# auxDaqUnitTop2022.net
KiCad netlist of a schematic drawn in EAGLE
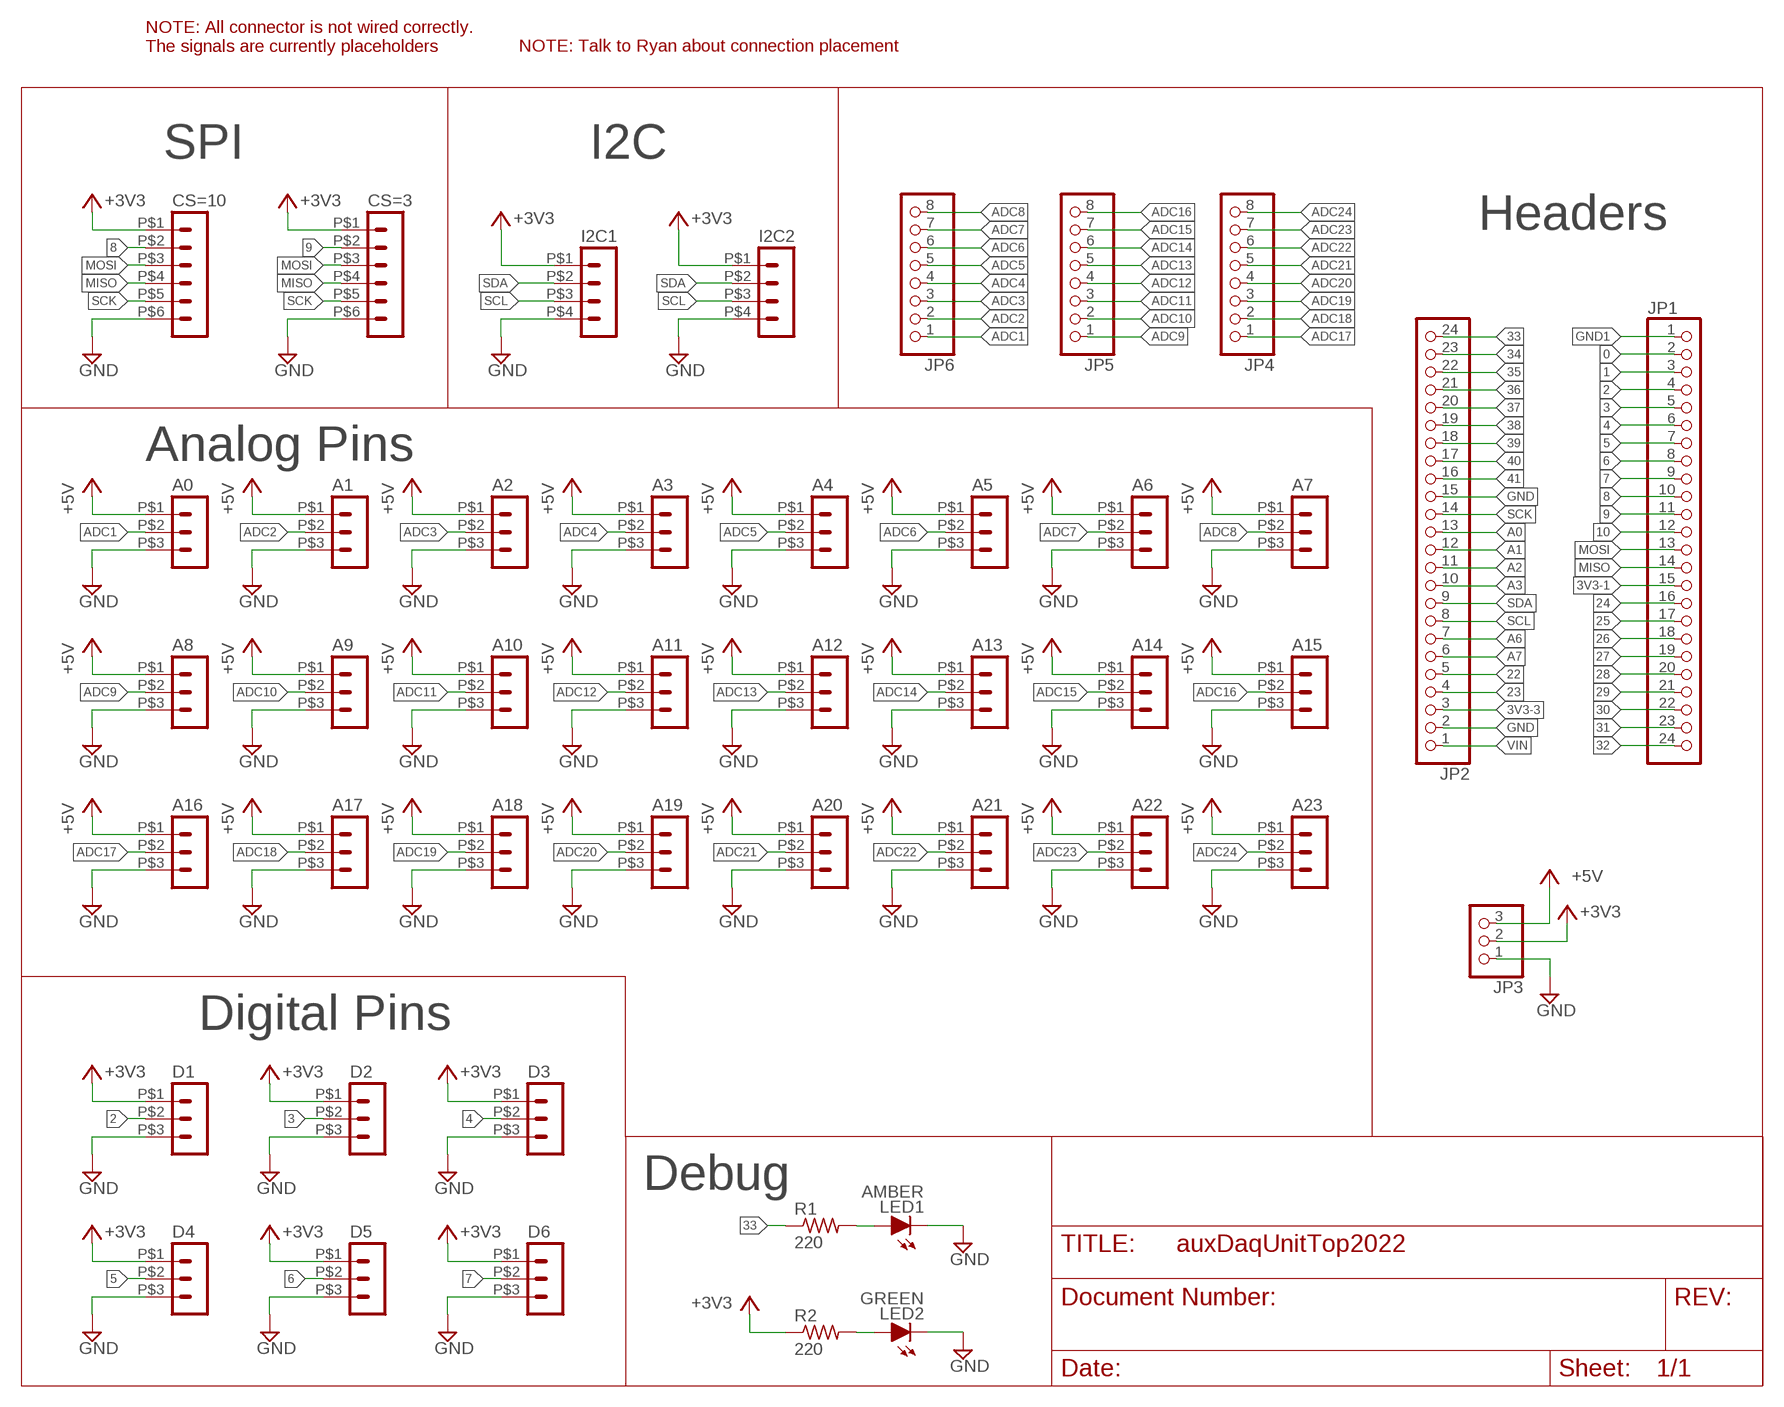
[diagram p0: schematic, sheet 1]

(export (version "E")
  (design (tool "Eeschema 10.0.6"))
  (components
    (comp (ref "A0")
      (value "HEADER_POS3_43650-0300")
      (footprint "eagle-import:43650-0300")
      (libsource (lib "eagle-import") (part "HEADER_POS3_?43650-0300"))
    )
    (comp (ref "A1")
      (value "HEADER_POS3_43650-0300")
      (footprint "eagle-import:43650-0300")
      (libsource (lib "eagle-import") (part "HEADER_POS3_?43650-0300"))
    )
    (comp (ref "A2")
      (value "HEADER_POS3_43650-0300")
      (footprint "eagle-import:43650-0300")
      (libsource (lib "eagle-import") (part "HEADER_POS3_?43650-0300"))
    )
    (comp (ref "A3")
      (value "HEADER_POS3_43650-0300")
      (footprint "eagle-import:43650-0300")
      (libsource (lib "eagle-import") (part "HEADER_POS3_?43650-0300"))
    )
    (comp (ref "A4")
      (value "HEADER_POS3_43650-0300")
      (footprint "eagle-import:43650-0300")
      (libsource (lib "eagle-import") (part "HEADER_POS3_?43650-0300"))
    )
    (comp (ref "A5")
      (value "HEADER_POS3_43650-0300")
      (footprint "eagle-import:43650-0300")
      (libsource (lib "eagle-import") (part "HEADER_POS3_?43650-0300"))
    )
    (comp (ref "A6")
      (value "HEADER_POS3_43650-0300")
      (footprint "eagle-import:43650-0300")
      (libsource (lib "eagle-import") (part "HEADER_POS3_?43650-0300"))
    )
    (comp (ref "A7")
      (value "HEADER_POS3_43650-0300")
      (footprint "eagle-import:43650-0300")
      (libsource (lib "eagle-import") (part "HEADER_POS3_?43650-0300"))
    )
    (comp (ref "A8")
      (value "HEADER_POS3_43650-0300")
      (footprint "eagle-import:43650-0300")
      (libsource (lib "eagle-import") (part "HEADER_POS3_?43650-0300"))
    )
    (comp (ref "A9")
      (value "HEADER_POS3_43650-0300")
      (footprint "eagle-import:43650-0300")
      (libsource (lib "eagle-import") (part "HEADER_POS3_?43650-0300"))
    )
    (comp (ref "A10")
      (value "HEADER_POS3_43650-0300")
      (footprint "eagle-import:43650-0300")
      (libsource (lib "eagle-import") (part "HEADER_POS3_?43650-0300"))
    )
    (comp (ref "A11")
      (value "HEADER_POS3_43650-0300")
      (footprint "eagle-import:43650-0300")
      (libsource (lib "eagle-import") (part "HEADER_POS3_?43650-0300"))
    )
    (comp (ref "A12")
      (value "HEADER_POS3_43650-0300")
      (footprint "eagle-import:43650-0300")
      (libsource (lib "eagle-import") (part "HEADER_POS3_?43650-0300"))
    )
    (comp (ref "A13")
      (value "HEADER_POS3_43650-0300")
      (footprint "eagle-import:43650-0300")
      (libsource (lib "eagle-import") (part "HEADER_POS3_?43650-0300"))
    )
    (comp (ref "A14")
      (value "HEADER_POS3_43650-0300")
      (footprint "eagle-import:43650-0300")
      (libsource (lib "eagle-import") (part "HEADER_POS3_?43650-0300"))
    )
    (comp (ref "A15")
      (value "HEADER_POS3_43650-0300")
      (footprint "eagle-import:43650-0300")
      (libsource (lib "eagle-import") (part "HEADER_POS3_?43650-0300"))
    )
    (comp (ref "A16")
      (value "HEADER_POS3_43650-0300")
      (footprint "eagle-import:43650-0300")
      (libsource (lib "eagle-import") (part "HEADER_POS3_?43650-0300"))
    )
    (comp (ref "A17")
      (value "HEADER_POS3_43650-0300")
      (footprint "eagle-import:43650-0300")
      (libsource (lib "eagle-import") (part "HEADER_POS3_?43650-0300"))
    )
    (comp (ref "A18")
      (value "HEADER_POS3_43650-0300")
      (footprint "eagle-import:43650-0300")
      (libsource (lib "eagle-import") (part "HEADER_POS3_?43650-0300"))
    )
    (comp (ref "A19")
      (value "HEADER_POS3_43650-0300")
      (footprint "eagle-import:43650-0300")
      (libsource (lib "eagle-import") (part "HEADER_POS3_?43650-0300"))
    )
    (comp (ref "A20")
      (value "HEADER_POS3_43650-0300")
      (footprint "eagle-import:43650-0300")
      (libsource (lib "eagle-import") (part "HEADER_POS3_?43650-0300"))
    )
    (comp (ref "A21")
      (value "HEADER_POS3_43650-0300")
      (footprint "eagle-import:43650-0300")
      (libsource (lib "eagle-import") (part "HEADER_POS3_?43650-0300"))
    )
    (comp (ref "A22")
      (value "HEADER_POS3_43650-0300")
      (footprint "eagle-import:43650-0300")
      (libsource (lib "eagle-import") (part "HEADER_POS3_?43650-0300"))
    )
    (comp (ref "A23")
      (value "HEADER_POS3_43650-0300")
      (footprint "eagle-import:43650-0300")
      (libsource (lib "eagle-import") (part "HEADER_POS3_?43650-0300"))
    )
    (comp (ref "CS=3")
      (value "HEADER_POS6_43045-0600")
      (footprint "eagle-import:43045-0600")
      (libsource (lib "eagle-import") (part "HEADER_POS6_?43045-0600"))
    )
    (comp (ref "CS=10")
      (value "HEADER_POS6_43045-0600")
      (footprint "eagle-import:43045-0600")
      (libsource (lib "eagle-import") (part "HEADER_POS6_?43045-0600"))
    )
    (comp (ref "D1")
      (value "HEADER_POS3_43650-0300")
      (footprint "eagle-import:43650-0300")
      (libsource (lib "eagle-import") (part "HEADER_POS3_?43650-0300"))
    )
    (comp (ref "D2")
      (value "HEADER_POS3_43650-0300")
      (footprint "eagle-import:43650-0300")
      (libsource (lib "eagle-import") (part "HEADER_POS3_?43650-0300"))
    )
    (comp (ref "D3")
      (value "HEADER_POS3_43650-0300")
      (footprint "eagle-import:43650-0300")
      (libsource (lib "eagle-import") (part "HEADER_POS3_?43650-0300"))
    )
    (comp (ref "D4")
      (value "HEADER_POS3_43650-0300")
      (footprint "eagle-import:43650-0300")
      (libsource (lib "eagle-import") (part "HEADER_POS3_?43650-0300"))
    )
    (comp (ref "D5")
      (value "HEADER_POS3_43650-0300")
      (footprint "eagle-import:43650-0300")
      (libsource (lib "eagle-import") (part "HEADER_POS3_?43650-0300"))
    )
    (comp (ref "D6")
      (value "HEADER_POS3_43650-0300")
      (footprint "eagle-import:43650-0300")
      (libsource (lib "eagle-import") (part "HEADER_POS3_?43650-0300"))
    )
    (comp (ref "I2C1")
      (value "HEADER_POS4_43045-0401")
      (footprint "eagle-import:43045-0400")
      (libsource (lib "eagle-import") (part "HEADER_POS4_?43045-0401"))
    )
    (comp (ref "I2C2")
      (value "HEADER_POS4_43045-0401")
      (footprint "eagle-import:43045-0400")
      (libsource (lib "eagle-import") (part "HEADER_POS4_?43045-0401"))
    )
    (comp (ref "JP1")
      (value "PINHD-1X24")
      (footprint "eagle-import:1X24")
      (libsource (lib "eagle-import") (part "PINHD-1X24"))
    )
    (comp (ref "JP2")
      (value "PINHD-1X24")
      (footprint "eagle-import:1X24")
      (libsource (lib "eagle-import") (part "PINHD-1X24"))
    )
    (comp (ref "JP3")
      (value "PINHD-1X3")
      (footprint "eagle-import:1X03")
      (libsource (lib "eagle-import") (part "PINHD-1X3"))
    )
    (comp (ref "JP4")
      (value "PINHD-1X8")
      (footprint "eagle-import:1X08")
      (libsource (lib "eagle-import") (part "PINHD-1X8"))
    )
    (comp (ref "JP5")
      (value "PINHD-1X8")
      (footprint "eagle-import:1X08")
      (libsource (lib "eagle-import") (part "PINHD-1X8"))
    )
    (comp (ref "JP6")
      (value "PINHD-1X8")
      (footprint "eagle-import:1X08")
      (libsource (lib "eagle-import") (part "PINHD-1X8"))
    )
    (comp (ref "LED1")
      (value "AMBER")
      (footprint "eagle-import:LED-603")
      (libsource (lib "eagle-import") (part "LED-0603"))
    )
    (comp (ref "LED2")
      (value "GREEN")
      (footprint "eagle-import:LED-603")
      (libsource (lib "eagle-import") (part "LED-0603"))
    )
    (comp (ref "R1")
      (value "220")
      (footprint "eagle-import:R0603")
      (libsource (lib "eagle-import") (part "RES_SMDR0603"))
    )
    (comp (ref "R2")
      (value "220")
      (footprint "eagle-import:R0603")
      (libsource (lib "eagle-import") (part "RES_SMDR0603"))
    )
  )
  (nets
    (net (code "1") (name "+3V3") (class "Default")
      (node (ref "CS=10") (pin "P$1") (pinfunction "1_P$1") (pintype "passive"))
      (node (ref "CS=3") (pin "P$1") (pinfunction "1_P$1") (pintype "passive"))
      (node (ref "D1") (pin "P$1") (pinfunction "1_P$1") (pintype "passive"))
      (node (ref "D2") (pin "P$1") (pinfunction "1_P$1") (pintype "passive"))
      (node (ref "D3") (pin "P$1") (pinfunction "1_P$1") (pintype "passive"))
      (node (ref "D4") (pin "P$1") (pinfunction "1_P$1") (pintype "passive"))
      (node (ref "D5") (pin "P$1") (pinfunction "1_P$1") (pintype "passive"))
      (node (ref "D6") (pin "P$1") (pinfunction "1_P$1") (pintype "passive"))
      (node (ref "I2C1") (pin "P$1") (pinfunction "1_P$1") (pintype "passive"))
      (node (ref "I2C2") (pin "P$1") (pinfunction "1_P$1") (pintype "passive"))
      (node (ref "JP3") (pin "2") (pinfunction "2_2") (pintype "passive"))
      (node (ref "R2") (pin "1") (pinfunction "1_1") (pintype "passive"))
    )
    (net (code "2") (name "+5V") (class "Default")
      (node (ref "A0") (pin "P$1") (pinfunction "1_P$1") (pintype "passive"))
      (node (ref "A1") (pin "P$1") (pinfunction "1_P$1") (pintype "passive"))
      (node (ref "A10") (pin "P$1") (pinfunction "1_P$1") (pintype "passive"))
      (node (ref "A11") (pin "P$1") (pinfunction "1_P$1") (pintype "passive"))
      (node (ref "A12") (pin "P$1") (pinfunction "1_P$1") (pintype "passive"))
      (node (ref "A13") (pin "P$1") (pinfunction "1_P$1") (pintype "passive"))
      (node (ref "A14") (pin "P$1") (pinfunction "1_P$1") (pintype "passive"))
      (node (ref "A15") (pin "P$1") (pinfunction "1_P$1") (pintype "passive"))
      (node (ref "A16") (pin "P$1") (pinfunction "1_P$1") (pintype "passive"))
      (node (ref "A17") (pin "P$1") (pinfunction "1_P$1") (pintype "passive"))
      (node (ref "A18") (pin "P$1") (pinfunction "1_P$1") (pintype "passive"))
      (node (ref "A19") (pin "P$1") (pinfunction "1_P$1") (pintype "passive"))
      (node (ref "A2") (pin "P$1") (pinfunction "1_P$1") (pintype "passive"))
      (node (ref "A20") (pin "P$1") (pinfunction "1_P$1") (pintype "passive"))
      (node (ref "A21") (pin "P$1") (pinfunction "1_P$1") (pintype "passive"))
      (node (ref "A22") (pin "P$1") (pinfunction "1_P$1") (pintype "passive"))
      (node (ref "A23") (pin "P$1") (pinfunction "1_P$1") (pintype "passive"))
      (node (ref "A3") (pin "P$1") (pinfunction "1_P$1") (pintype "passive"))
      (node (ref "A4") (pin "P$1") (pinfunction "1_P$1") (pintype "passive"))
      (node (ref "A5") (pin "P$1") (pinfunction "1_P$1") (pintype "passive"))
      (node (ref "A6") (pin "P$1") (pinfunction "1_P$1") (pintype "passive"))
      (node (ref "A7") (pin "P$1") (pinfunction "1_P$1") (pintype "passive"))
      (node (ref "A8") (pin "P$1") (pinfunction "1_P$1") (pintype "passive"))
      (node (ref "A9") (pin "P$1") (pinfunction "1_P$1") (pintype "passive"))
      (node (ref "JP3") (pin "3") (pinfunction "3_3") (pintype "passive"))
    )
    (net (code "3") (name "0") (class "Default")
      (node (ref "JP1") (pin "2") (pinfunction "2_2") (pintype "passive"))
    )
    (net (code "4") (name "1") (class "Default")
      (node (ref "JP1") (pin "3") (pinfunction "3_3") (pintype "passive"))
    )
    (net (code "5") (name "2") (class "Default")
      (node (ref "D1") (pin "P$2") (pinfunction "2_P$2") (pintype "passive"))
      (node (ref "JP1") (pin "4") (pinfunction "4_4") (pintype "passive"))
    )
    (net (code "6") (name "3") (class "Default")
      (node (ref "D2") (pin "P$2") (pinfunction "2_P$2") (pintype "passive"))
      (node (ref "JP1") (pin "5") (pinfunction "5_5") (pintype "passive"))
    )
    (net (code "7") (name "3V3-1") (class "Default")
      (node (ref "JP1") (pin "15") (pinfunction "15_15") (pintype "passive"))
    )
    (net (code "8") (name "3V3-3") (class "Default")
      (node (ref "JP2") (pin "3") (pinfunction "3_3") (pintype "passive"))
    )
    (net (code "9") (name "4") (class "Default")
      (node (ref "D3") (pin "P$2") (pinfunction "2_P$2") (pintype "passive"))
      (node (ref "JP1") (pin "6") (pinfunction "6_6") (pintype "passive"))
    )
    (net (code "10") (name "5") (class "Default")
      (node (ref "D4") (pin "P$2") (pinfunction "2_P$2") (pintype "passive"))
      (node (ref "JP1") (pin "7") (pinfunction "7_7") (pintype "passive"))
    )
    (net (code "11") (name "6") (class "Default")
      (node (ref "D5") (pin "P$2") (pinfunction "2_P$2") (pintype "passive"))
      (node (ref "JP1") (pin "8") (pinfunction "8_8") (pintype "passive"))
    )
    (net (code "12") (name "7") (class "Default")
      (node (ref "D6") (pin "P$2") (pinfunction "2_P$2") (pintype "passive"))
      (node (ref "JP1") (pin "9") (pinfunction "9_9") (pintype "passive"))
    )
    (net (code "13") (name "8") (class "Default")
      (node (ref "CS=10") (pin "P$2") (pinfunction "2_P$2") (pintype "passive"))
      (node (ref "JP1") (pin "10") (pinfunction "10_10") (pintype "passive"))
    )
    (net (code "14") (name "9") (class "Default")
      (node (ref "CS=3") (pin "P$2") (pinfunction "2_P$2") (pintype "passive"))
      (node (ref "JP1") (pin "11") (pinfunction "11_11") (pintype "passive"))
    )
    (net (code "15") (name "10") (class "Default")
      (node (ref "JP1") (pin "12") (pinfunction "12_12") (pintype "passive"))
    )
    (net (code "16") (name "22") (class "Default")
      (node (ref "JP2") (pin "5") (pinfunction "5_5") (pintype "passive"))
    )
    (net (code "17") (name "23") (class "Default")
      (node (ref "JP2") (pin "4") (pinfunction "4_4") (pintype "passive"))
    )
    (net (code "18") (name "24") (class "Default")
      (node (ref "JP1") (pin "16") (pinfunction "16_16") (pintype "passive"))
    )
    (net (code "19") (name "25") (class "Default")
      (node (ref "JP1") (pin "17") (pinfunction "17_17") (pintype "passive"))
    )
    (net (code "20") (name "26") (class "Default")
      (node (ref "JP1") (pin "18") (pinfunction "18_18") (pintype "passive"))
    )
    (net (code "21") (name "27") (class "Default")
      (node (ref "JP1") (pin "19") (pinfunction "19_19") (pintype "passive"))
    )
    (net (code "22") (name "28") (class "Default")
      (node (ref "JP1") (pin "20") (pinfunction "20_20") (pintype "passive"))
    )
    (net (code "23") (name "29") (class "Default")
      (node (ref "JP1") (pin "21") (pinfunction "21_21") (pintype "passive"))
    )
    (net (code "24") (name "30") (class "Default")
      (node (ref "JP1") (pin "22") (pinfunction "22_22") (pintype "passive"))
    )
    (net (code "25") (name "31") (class "Default")
      (node (ref "JP1") (pin "23") (pinfunction "23_23") (pintype "passive"))
    )
    (net (code "26") (name "32") (class "Default")
      (node (ref "JP1") (pin "24") (pinfunction "24_24") (pintype "passive"))
    )
    (net (code "27") (name "33") (class "Default")
      (node (ref "JP2") (pin "24") (pinfunction "24_24") (pintype "passive"))
      (node (ref "R1") (pin "1") (pinfunction "1_1") (pintype "passive"))
    )
    (net (code "28") (name "34") (class "Default")
      (node (ref "JP2") (pin "23") (pinfunction "23_23") (pintype "passive"))
    )
    (net (code "29") (name "35") (class "Default")
      (node (ref "JP2") (pin "22") (pinfunction "22_22") (pintype "passive"))
    )
    (net (code "30") (name "36") (class "Default")
      (node (ref "JP2") (pin "21") (pinfunction "21_21") (pintype "passive"))
    )
    (net (code "31") (name "37") (class "Default")
      (node (ref "JP2") (pin "20") (pinfunction "20_20") (pintype "passive"))
    )
    (net (code "32") (name "38") (class "Default")
      (node (ref "JP2") (pin "19") (pinfunction "19_19") (pintype "passive"))
    )
    (net (code "33") (name "39") (class "Default")
      (node (ref "JP2") (pin "18") (pinfunction "18_18") (pintype "passive"))
    )
    (net (code "34") (name "40") (class "Default")
      (node (ref "JP2") (pin "17") (pinfunction "17_17") (pintype "passive"))
    )
    (net (code "35") (name "41") (class "Default")
      (node (ref "JP2") (pin "16") (pinfunction "16_16") (pintype "passive"))
    )
    (net (code "36") (name "A0") (class "Default")
      (node (ref "JP2") (pin "13") (pinfunction "13_13") (pintype "passive"))
    )
    (net (code "37") (name "A1") (class "Default")
      (node (ref "JP2") (pin "12") (pinfunction "12_12") (pintype "passive"))
    )
    (net (code "38") (name "A2") (class "Default")
      (node (ref "JP2") (pin "11") (pinfunction "11_11") (pintype "passive"))
    )
    (net (code "39") (name "A3") (class "Default")
      (node (ref "JP2") (pin "10") (pinfunction "10_10") (pintype "passive"))
    )
    (net (code "40") (name "A6") (class "Default")
      (node (ref "JP2") (pin "7") (pinfunction "7_7") (pintype "passive"))
    )
    (net (code "41") (name "A7") (class "Default")
      (node (ref "JP2") (pin "6") (pinfunction "6_6") (pintype "passive"))
    )
    (net (code "42") (name "ADC1") (class "Default")
      (node (ref "A0") (pin "P$2") (pinfunction "2_P$2") (pintype "passive"))
      (node (ref "JP6") (pin "1") (pinfunction "1_1") (pintype "passive"))
    )
    (net (code "43") (name "ADC2") (class "Default")
      (node (ref "A1") (pin "P$2") (pinfunction "2_P$2") (pintype "passive"))
      (node (ref "JP6") (pin "2") (pinfunction "2_2") (pintype "passive"))
    )
    (net (code "44") (name "ADC3") (class "Default")
      (node (ref "A2") (pin "P$2") (pinfunction "2_P$2") (pintype "passive"))
      (node (ref "JP6") (pin "3") (pinfunction "3_3") (pintype "passive"))
    )
    (net (code "45") (name "ADC4") (class "Default")
      (node (ref "A3") (pin "P$2") (pinfunction "2_P$2") (pintype "passive"))
      (node (ref "JP6") (pin "4") (pinfunction "4_4") (pintype "passive"))
    )
    (net (code "46") (name "ADC5") (class "Default")
      (node (ref "A4") (pin "P$2") (pinfunction "2_P$2") (pintype "passive"))
      (node (ref "JP6") (pin "5") (pinfunction "5_5") (pintype "passive"))
    )
    (net (code "47") (name "ADC6") (class "Default")
      (node (ref "A5") (pin "P$2") (pinfunction "2_P$2") (pintype "passive"))
      (node (ref "JP6") (pin "6") (pinfunction "6_6") (pintype "passive"))
    )
    (net (code "48") (name "ADC7") (class "Default")
      (node (ref "A6") (pin "P$2") (pinfunction "2_P$2") (pintype "passive"))
      (node (ref "JP6") (pin "7") (pinfunction "7_7") (pintype "passive"))
    )
    (net (code "49") (name "ADC8") (class "Default")
      (node (ref "A7") (pin "P$2") (pinfunction "2_P$2") (pintype "passive"))
      (node (ref "JP6") (pin "8") (pinfunction "8_8") (pintype "passive"))
    )
    (net (code "50") (name "ADC9") (class "Default")
      (node (ref "A8") (pin "P$2") (pinfunction "2_P$2") (pintype "passive"))
      (node (ref "JP5") (pin "1") (pinfunction "1_1") (pintype "passive"))
    )
    (net (code "51") (name "ADC10") (class "Default")
      (node (ref "A9") (pin "P$2") (pinfunction "2_P$2") (pintype "passive"))
      (node (ref "JP5") (pin "2") (pinfunction "2_2") (pintype "passive"))
    )
    (net (code "52") (name "ADC11") (class "Default")
      (node (ref "A10") (pin "P$2") (pinfunction "2_P$2") (pintype "passive"))
      (node (ref "JP5") (pin "3") (pinfunction "3_3") (pintype "passive"))
    )
    (net (code "53") (name "ADC12") (class "Default")
      (node (ref "A11") (pin "P$2") (pinfunction "2_P$2") (pintype "passive"))
      (node (ref "JP5") (pin "4") (pinfunction "4_4") (pintype "passive"))
    )
    (net (code "54") (name "ADC13") (class "Default")
      (node (ref "A12") (pin "P$2") (pinfunction "2_P$2") (pintype "passive"))
      (node (ref "JP5") (pin "5") (pinfunction "5_5") (pintype "passive"))
    )
    (net (code "55") (name "ADC14") (class "Default")
      (node (ref "A13") (pin "P$2") (pinfunction "2_P$2") (pintype "passive"))
      (node (ref "JP5") (pin "6") (pinfunction "6_6") (pintype "passive"))
    )
    (net (code "56") (name "ADC15") (class "Default")
      (node (ref "A14") (pin "P$2") (pinfunction "2_P$2") (pintype "passive"))
      (node (ref "JP5") (pin "7") (pinfunction "7_7") (pintype "passive"))
    )
    (net (code "57") (name "ADC16") (class "Default")
      (node (ref "A15") (pin "P$2") (pinfunction "2_P$2") (pintype "passive"))
      (node (ref "JP5") (pin "8") (pinfunction "8_8") (pintype "passive"))
    )
    (net (code "58") (name "ADC17") (class "Default")
      (node (ref "A16") (pin "P$2") (pinfunction "2_P$2") (pintype "passive"))
      (node (ref "JP4") (pin "1") (pinfunction "1_1") (pintype "passive"))
    )
    (net (code "59") (name "ADC18") (class "Default")
      (node (ref "A17") (pin "P$2") (pinfunction "2_P$2") (pintype "passive"))
      (node (ref "JP4") (pin "2") (pinfunction "2_2") (pintype "passive"))
    )
    (net (code "60") (name "ADC19") (class "Default")
      (node (ref "A18") (pin "P$2") (pinfunction "2_P$2") (pintype "passive"))
      (node (ref "JP4") (pin "3") (pinfunction "3_3") (pintype "passive"))
    )
    (net (code "61") (name "ADC20") (class "Default")
      (node (ref "A19") (pin "P$2") (pinfunction "2_P$2") (pintype "passive"))
      (node (ref "JP4") (pin "4") (pinfunction "4_4") (pintype "passive"))
    )
    (net (code "62") (name "ADC21") (class "Default")
      (node (ref "A20") (pin "P$2") (pinfunction "2_P$2") (pintype "passive"))
      (node (ref "JP4") (pin "5") (pinfunction "5_5") (pintype "passive"))
    )
    (net (code "63") (name "ADC22") (class "Default")
      (node (ref "A21") (pin "P$2") (pinfunction "2_P$2") (pintype "passive"))
      (node (ref "JP4") (pin "6") (pinfunction "6_6") (pintype "passive"))
    )
    (net (code "64") (name "ADC23") (class "Default")
      (node (ref "A22") (pin "P$2") (pinfunction "2_P$2") (pintype "passive"))
      (node (ref "JP4") (pin "7") (pinfunction "7_7") (pintype "passive"))
    )
    (net (code "65") (name "ADC24") (class "Default")
      (node (ref "A23") (pin "P$2") (pinfunction "2_P$2") (pintype "passive"))
      (node (ref "JP4") (pin "8") (pinfunction "8_8") (pintype "passive"))
    )
    (net (code "66") (name "GND") (class "Default")
      (node (ref "A0") (pin "P$3") (pinfunction "3_P$3") (pintype "passive"))
      (node (ref "A1") (pin "P$3") (pinfunction "3_P$3") (pintype "passive"))
      (node (ref "A10") (pin "P$3") (pinfunction "3_P$3") (pintype "passive"))
      (node (ref "A11") (pin "P$3") (pinfunction "3_P$3") (pintype "passive"))
      (node (ref "A12") (pin "P$3") (pinfunction "3_P$3") (pintype "passive"))
      (node (ref "A13") (pin "P$3") (pinfunction "3_P$3") (pintype "passive"))
      (node (ref "A14") (pin "P$3") (pinfunction "3_P$3") (pintype "passive"))
      (node (ref "A15") (pin "P$3") (pinfunction "3_P$3") (pintype "passive"))
      (node (ref "A16") (pin "P$3") (pinfunction "3_P$3") (pintype "passive"))
      (node (ref "A17") (pin "P$3") (pinfunction "3_P$3") (pintype "passive"))
      (node (ref "A18") (pin "P$3") (pinfunction "3_P$3") (pintype "passive"))
      (node (ref "A19") (pin "P$3") (pinfunction "3_P$3") (pintype "passive"))
      (node (ref "A2") (pin "P$3") (pinfunction "3_P$3") (pintype "passive"))
      (node (ref "A20") (pin "P$3") (pinfunction "3_P$3") (pintype "passive"))
      (node (ref "A21") (pin "P$3") (pinfunction "3_P$3") (pintype "passive"))
      (node (ref "A22") (pin "P$3") (pinfunction "3_P$3") (pintype "passive"))
      (node (ref "A23") (pin "P$3") (pinfunction "3_P$3") (pintype "passive"))
      (node (ref "A3") (pin "P$3") (pinfunction "3_P$3") (pintype "passive"))
      (node (ref "A4") (pin "P$3") (pinfunction "3_P$3") (pintype "passive"))
      (node (ref "A5") (pin "P$3") (pinfunction "3_P$3") (pintype "passive"))
      (node (ref "A6") (pin "P$3") (pinfunction "3_P$3") (pintype "passive"))
      (node (ref "A7") (pin "P$3") (pinfunction "3_P$3") (pintype "passive"))
      (node (ref "A8") (pin "P$3") (pinfunction "3_P$3") (pintype "passive"))
      (node (ref "A9") (pin "P$3") (pinfunction "3_P$3") (pintype "passive"))
      (node (ref "CS=10") (pin "P$6") (pinfunction "6_P$6") (pintype "passive"))
      (node (ref "CS=3") (pin "P$6") (pinfunction "6_P$6") (pintype "passive"))
      (node (ref "D1") (pin "P$3") (pinfunction "3_P$3") (pintype "passive"))
      (node (ref "D2") (pin "P$3") (pinfunction "3_P$3") (pintype "passive"))
      (node (ref "D3") (pin "P$3") (pinfunction "3_P$3") (pintype "passive"))
      (node (ref "D4") (pin "P$3") (pinfunction "3_P$3") (pintype "passive"))
      (node (ref "D5") (pin "P$3") (pinfunction "3_P$3") (pintype "passive"))
      (node (ref "D6") (pin "P$3") (pinfunction "3_P$3") (pintype "passive"))
      (node (ref "I2C1") (pin "P$4") (pinfunction "4_P$4") (pintype "passive"))
      (node (ref "I2C2") (pin "P$4") (pinfunction "4_P$4") (pintype "passive"))
      (node (ref "JP2") (pin "15") (pinfunction "15_15") (pintype "passive"))
      (node (ref "JP2") (pin "2") (pinfunction "2_2") (pintype "passive"))
      (node (ref "JP3") (pin "1") (pinfunction "1_1") (pintype "passive"))
      (node (ref "LED1") (pin "C") (pinfunction "C_C") (pintype "passive"))
      (node (ref "LED2") (pin "C") (pinfunction "C_C") (pintype "passive"))
    )
    (net (code "67") (name "GND1") (class "Default")
      (node (ref "JP1") (pin "1") (pinfunction "1_1") (pintype "passive"))
    )
    (net (code "68") (name "MISO") (class "Default")
      (node (ref "CS=10") (pin "P$4") (pinfunction "4_P$4") (pintype "passive"))
      (node (ref "CS=3") (pin "P$4") (pinfunction "4_P$4") (pintype "passive"))
      (node (ref "JP1") (pin "14") (pinfunction "14_14") (pintype "passive"))
    )
    (net (code "69") (name "MOSI") (class "Default")
      (node (ref "CS=10") (pin "P$3") (pinfunction "3_P$3") (pintype "passive"))
      (node (ref "CS=3") (pin "P$3") (pinfunction "3_P$3") (pintype "passive"))
      (node (ref "JP1") (pin "13") (pinfunction "13_13") (pintype "passive"))
    )
    (net (code "70") (name "Net-(LED1-PadA)") (class "Default")
      (node (ref "LED1") (pin "A") (pinfunction "A_A") (pintype "passive"))
      (node (ref "R1") (pin "2") (pinfunction "2_2") (pintype "passive"))
    )
    (net (code "71") (name "Net-(LED2-PadA)") (class "Default")
      (node (ref "LED2") (pin "A") (pinfunction "A_A") (pintype "passive"))
      (node (ref "R2") (pin "2") (pinfunction "2_2") (pintype "passive"))
    )
    (net (code "72") (name "SCK") (class "Default")
      (node (ref "CS=10") (pin "P$5") (pinfunction "5_P$5") (pintype "passive"))
      (node (ref "CS=3") (pin "P$5") (pinfunction "5_P$5") (pintype "passive"))
      (node (ref "JP2") (pin "14") (pinfunction "14_14") (pintype "passive"))
    )
    (net (code "73") (name "SCL") (class "Default")
      (node (ref "I2C1") (pin "P$3") (pinfunction "3_P$3") (pintype "passive"))
      (node (ref "I2C2") (pin "P$3") (pinfunction "3_P$3") (pintype "passive"))
      (node (ref "JP2") (pin "8") (pinfunction "8_8") (pintype "passive"))
    )
    (net (code "74") (name "SDA") (class "Default")
      (node (ref "I2C1") (pin "P$2") (pinfunction "2_P$2") (pintype "passive"))
      (node (ref "I2C2") (pin "P$2") (pinfunction "2_P$2") (pintype "passive"))
      (node (ref "JP2") (pin "9") (pinfunction "9_9") (pintype "passive"))
    )
    (net (code "75") (name "VIN") (class "Default")
      (node (ref "JP2") (pin "1") (pinfunction "1_1") (pintype "passive"))
    )
  )
)
